# 04_Mechanical.net
KiCad netlist of a schematic drawn in Altium Designer
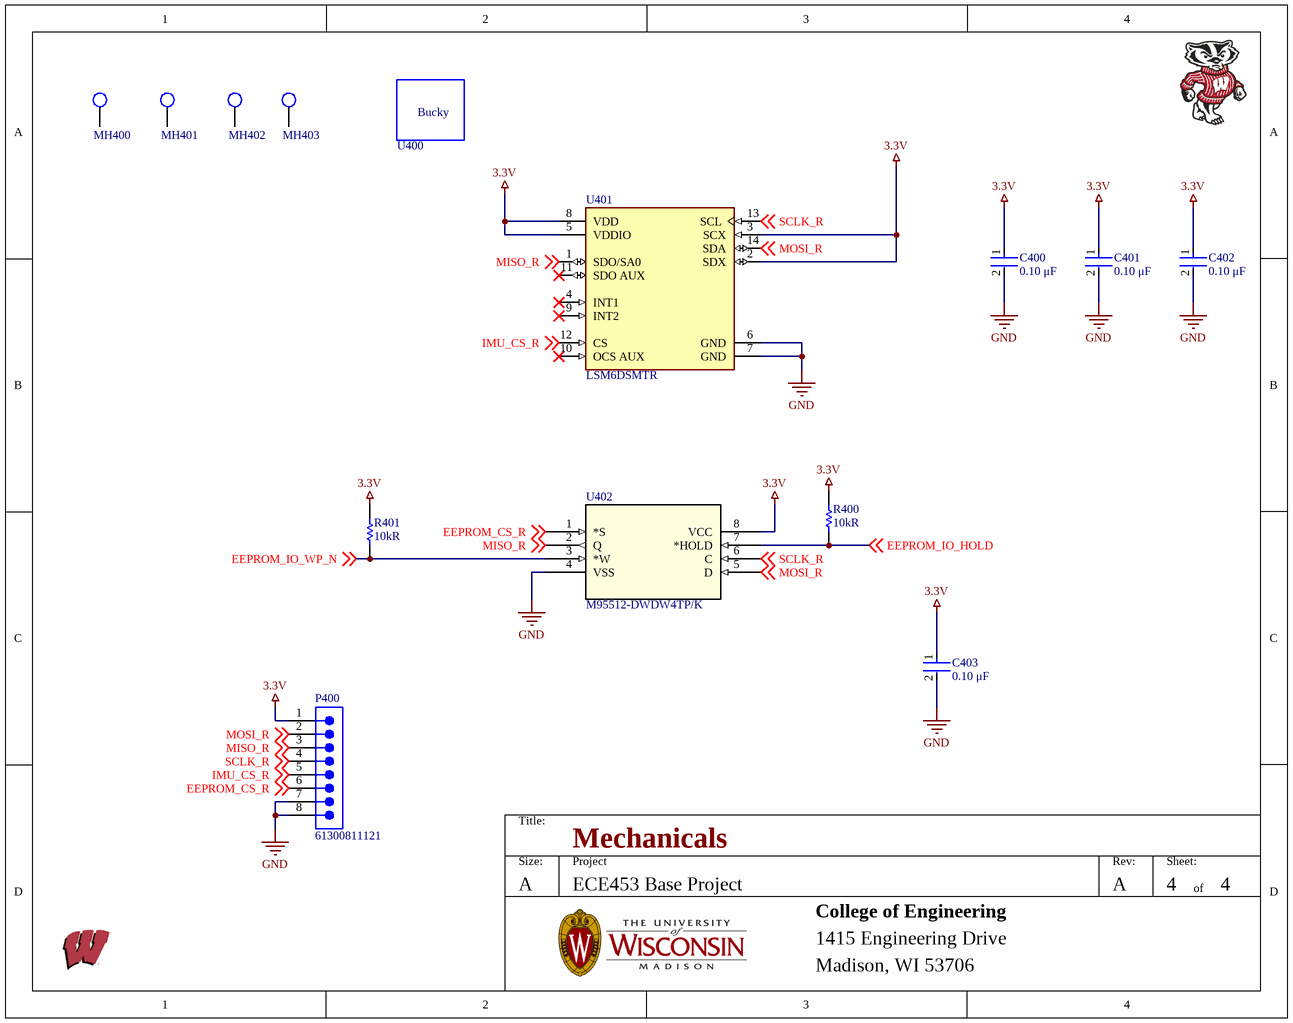
[diagram p0: 04_Mechanical.SchDoc]

(export (version "E")
  (design (tool "Eeschema 10.0.6"))
  (components
    (comp (ref "C400")
      (value "0.10 μF")
      (footprint "FP-C0805C-DN-MFG")
      (description "CAP CER 0.1UF 50V X7R 0805")
      (fields
        (field (name "MANUFACTURER PART NUMBER") "C0805C104K5RACTU")
        (field (name "MANUFACTURER") "KEMET")
      )
      (libsource (lib "Altium Content Vault") (part "b4654b650e69147ec39a6b967a45e02"))
    )
    (comp (ref "C401")
      (value "0.10 μF")
      (footprint "FP-C0805C-DN-MFG")
      (description "CAP CER 0.1UF 50V X7R 0805")
      (fields
        (field (name "MANUFACTURER PART NUMBER") "C0805C104K5RACTU")
        (field (name "MANUFACTURER") "KEMET")
      )
      (libsource (lib "Altium Content Vault") (part "b4654b650e69147ec39a6b967a45e02"))
    )
    (comp (ref "C402")
      (value "0.10 μF")
      (footprint "FP-C0805C-DN-MFG")
      (description "CAP CER 0.1UF 50V X7R 0805")
      (fields
        (field (name "MANUFACTURER PART NUMBER") "C0805C104K5RACTU")
        (field (name "MANUFACTURER") "KEMET")
      )
      (libsource (lib "Altium Content Vault") (part "b4654b650e69147ec39a6b967a45e02"))
    )
    (comp (ref "C403")
      (value "0.10 μF")
      (footprint "FP-C0805C-DN-MFG")
      (description "CAP CER 0.1UF 50V X7R 0805")
      (fields
        (field (name "MANUFACTURER PART NUMBER") "C0805C104K5RACTU")
        (field (name "MANUFACTURER") "KEMET")
      )
      (libsource (lib "Altium Content Vault") (part "b4654b650e69147ec39a6b967a45e02"))
    )
    (comp (ref "MH400")
      (value "MHOLE_2_55MM")
      (footprint "MHOLE_2_55MM")
      (description "Mounting Holde")
      (fields (field (name "MANUFACTURER PART NUMBER") "UW MTHOLE"))
      (libsource (lib "ECE453_S24") (part "MHOLE_2_55MM"))
    )
    (comp (ref "MH401")
      (value "MHOLE_2_55MM")
      (footprint "MHOLE_2_55MM")
      (description "Mounting Holde")
      (fields (field (name "MANUFACTURER PART NUMBER") "UW MTHOLE"))
      (libsource (lib "ECE453_S24") (part "MHOLE_2_55MM"))
    )
    (comp (ref "MH402")
      (value "MHOLE_2_55MM")
      (footprint "MHOLE_2_55MM")
      (description "Mounting Holde")
      (fields (field (name "MANUFACTURER PART NUMBER") "UW MTHOLE"))
      (libsource (lib "ECE453_S24") (part "MHOLE_2_55MM"))
    )
    (comp (ref "MH403")
      (value "MHOLE_2_55MM")
      (footprint "MHOLE_2_55MM")
      (description "Mounting Holde")
      (fields (field (name "MANUFACTURER PART NUMBER") "UW MTHOLE"))
      (libsource (lib "ECE453_S24") (part "MHOLE_2_55MM"))
    )
    (comp (ref "P400")
      (value "61300811121")
      (footprint "61300811121")
      (fields (field (name "MANUFACTURER") "Wurth Electronics"))
      (libsource (lib "Altium Content Vault") (part "Header_Male_1R_08P"))
    )
    (comp (ref "R400")
      (value "10kR")
      (footprint "RESC2013X70X40ML20T20")
      (fields
        (field (name "MANUFACTURER") "Panasonic")
        (field (name "PART NUMBER") "ERJ-6ENF1002V")
        (field (name "TOLERANCE") "1%")
      )
      (libsource (lib "Altium Content Vault") (part "RES"))
    )
    (comp (ref "R401")
      (value "10kR")
      (footprint "RESC2013X70X40ML20T20")
      (fields
        (field (name "MANUFACTURER") "Panasonic")
        (field (name "PART NUMBER") "ERJ-6ENF1002V")
        (field (name "TOLERANCE") "1%")
      )
      (libsource (lib "Altium Content Vault") (part "RES"))
    )
    (comp (ref "U400")
      (value "Bucky")
      (footprint "WalkingBucky")
      (description "Bucky Badger Image")
      (fields (field (name "MANUFACTURER PART NUMBER") "UW Bucky"))
      (libsource (lib "ECE453") (part "Bucky"))
    )
    (comp (ref "U401")
      (value "LSM6DSMTR")
      (footprint "FP-LGA-14L-DM00249496-MFG")
      (description "IMU ACCEL/GYRO I2C/SPI 14LGA")
      (fields
        (field (name "OCTOPART") "https://octopart.com/lsm6dsmtr-stmicroelectronics-66358194")
        (field (name "MANUFACTURER") "STMicroelectronics")
      )
      (libsource (lib "Altium Content Vault") (part "dd82ae232bae541fa9c740d21cb9072"))
    )
    (comp (ref "U402")
      (value "M95512-DWDW4TP/K")
      (footprint "TSSOP8_169MILS_DW_STM-M")
      (description "EEPROM Serial-SPI 512K-bit 64K x 8 3.3V/5V Automotive 8-Pin TSSOP T/R")
      (fields (field (name "COPYRIGHT") "Copyright (C) 2022 Ultra Librarian. All rights reserved."))
      (libsource (lib "ECE453_S24") (part "M95512-DWDW4TP/K"))
    )
  )
  (nets
    (net (code "1") (name "3.3V") (class "Default")
      (node (ref "C400") (pin "1") (pinfunction "1_1") (pintype "passive"))
      (node (ref "C401") (pin "1") (pinfunction "1_1") (pintype "passive"))
      (node (ref "C402") (pin "1") (pinfunction "1_1") (pintype "passive"))
      (node (ref "C403") (pin "1") (pinfunction "1_1") (pintype "passive"))
      (node (ref "P400") (pin "1") (pinfunction "1_1") (pintype "passive"))
      (node (ref "R400") (pin "2") (pinfunction "2_2") (pintype "passive"))
      (node (ref "R401") (pin "2") (pinfunction "2_2") (pintype "passive"))
      (node (ref "U401") (pin "2") (pinfunction "SDX_2") (pintype "bidirectional"))
      (node (ref "U401") (pin "3") (pinfunction "SCX_3") (pintype "input"))
      (node (ref "U401") (pin "5") (pinfunction "VDDIO_5") (pintype "power_in"))
      (node (ref "U401") (pin "8") (pinfunction "VDD_8") (pintype "power_in"))
      (node (ref "U402") (pin "8") (pinfunction "VCC_8") (pintype "power_in"))
    )
    (net (code "2") (name "EEPROM_CS_R") (class "Default")
      (node (ref "P400") (pin "6") (pinfunction "6_6") (pintype "passive"))
      (node (ref "U402") (pin "1") (pinfunction "*S_1") (pintype "input"))
    )
    (net (code "3") (name "EEPROM_IO_HOLD") (class "Default")
      (node (ref "R400") (pin "1") (pinfunction "1_1") (pintype "passive"))
      (node (ref "U402") (pin "7") (pinfunction "*HOLD_7") (pintype "input"))
    )
    (net (code "4") (name "EEPROM_IO_WP_N") (class "Default")
      (node (ref "R401") (pin "1") (pinfunction "1_1") (pintype "passive"))
      (node (ref "U402") (pin "3") (pinfunction "*W_3") (pintype "input"))
    )
    (net (code "5") (name "GND") (class "Default")
      (node (ref "C400") (pin "2") (pinfunction "2_2") (pintype "passive"))
      (node (ref "C401") (pin "2") (pinfunction "2_2") (pintype "passive"))
      (node (ref "C402") (pin "2") (pinfunction "2_2") (pintype "passive"))
      (node (ref "C403") (pin "2") (pinfunction "2_2") (pintype "passive"))
      (node (ref "P400") (pin "7") (pinfunction "7_7") (pintype "passive"))
      (node (ref "P400") (pin "8") (pinfunction "8_8") (pintype "passive"))
      (node (ref "U401") (pin "6") (pinfunction "GND_6") (pintype "power_in"))
      (node (ref "U401") (pin "7") (pinfunction "GND_7") (pintype "power_in"))
      (node (ref "U402") (pin "4") (pinfunction "VSS_4") (pintype "passive"))
    )
    (net (code "6") (name "IMU_CS_R") (class "Default")
      (node (ref "P400") (pin "5") (pinfunction "5_5") (pintype "passive"))
      (node (ref "U401") (pin "12") (pinfunction "CS_12") (pintype "input"))
    )
    (net (code "7") (name "MISO_R") (class "Default")
      (node (ref "P400") (pin "3") (pinfunction "3_3") (pintype "passive"))
      (node (ref "U401") (pin "1") (pinfunction "SDO/SA0_1") (pintype "bidirectional"))
      (node (ref "U402") (pin "2") (pinfunction "Q_2") (pintype "output"))
    )
    (net (code "8") (name "MOSI_R") (class "Default")
      (node (ref "P400") (pin "2") (pinfunction "2_2") (pintype "passive"))
      (node (ref "U401") (pin "14") (pinfunction "SDA_14") (pintype "bidirectional"))
      (node (ref "U402") (pin "5") (pinfunction "D_5") (pintype "input"))
    )
    (net (code "9") (name "SCLK_R") (class "Default")
      (node (ref "P400") (pin "4") (pinfunction "4_4") (pintype "passive"))
      (node (ref "U401") (pin "13") (pinfunction "SCL_13") (pintype "input"))
      (node (ref "U402") (pin "6") (pinfunction "C_6") (pintype "input"))
    )
    (net (code "10") (name "unconnected-(MH400-Pad1)") (class "Default")
      (node (ref "MH400") (pin "1") (pintype "passive"))
    )
    (net (code "11") (name "unconnected-(MH401-Pad1)") (class "Default")
      (node (ref "MH401") (pin "1") (pintype "passive"))
    )
    (net (code "12") (name "unconnected-(MH402-Pad1)") (class "Default")
      (node (ref "MH402") (pin "1") (pintype "passive"))
    )
    (net (code "13") (name "unconnected-(MH403-Pad1)") (class "Default")
      (node (ref "MH403") (pin "1") (pintype "passive"))
    )
    (net (code "14") (name "unconnected-(U401-INT1-Pad4)") (class "Default")
      (node (ref "U401") (pin "4") (pinfunction "INT1_4") (pintype "input+no_connect"))
    )
    (net (code "15") (name "unconnected-(U401-INT2-Pad9)") (class "Default")
      (node (ref "U401") (pin "9") (pinfunction "INT2_9") (pintype "input+no_connect"))
    )
    (net (code "16") (name "unconnected-(U401-OCS_AUX-Pad10)") (class "Default")
      (node (ref "U401") (pin "10") (pinfunction "OCS_AUX_10") (pintype "input+no_connect"))
    )
    (net (code "17") (name "unconnected-(U401-SDO_AUX-Pad11)") (class "Default")
      (node (ref "U401") (pin "11") (pinfunction "SDO_AUX_11") (pintype "bidirectional+no_connect"))
    )
  )
)
